# tsl3301cl_cs_mount.net
KiCad netlist of a schematic drawn in EAGLE
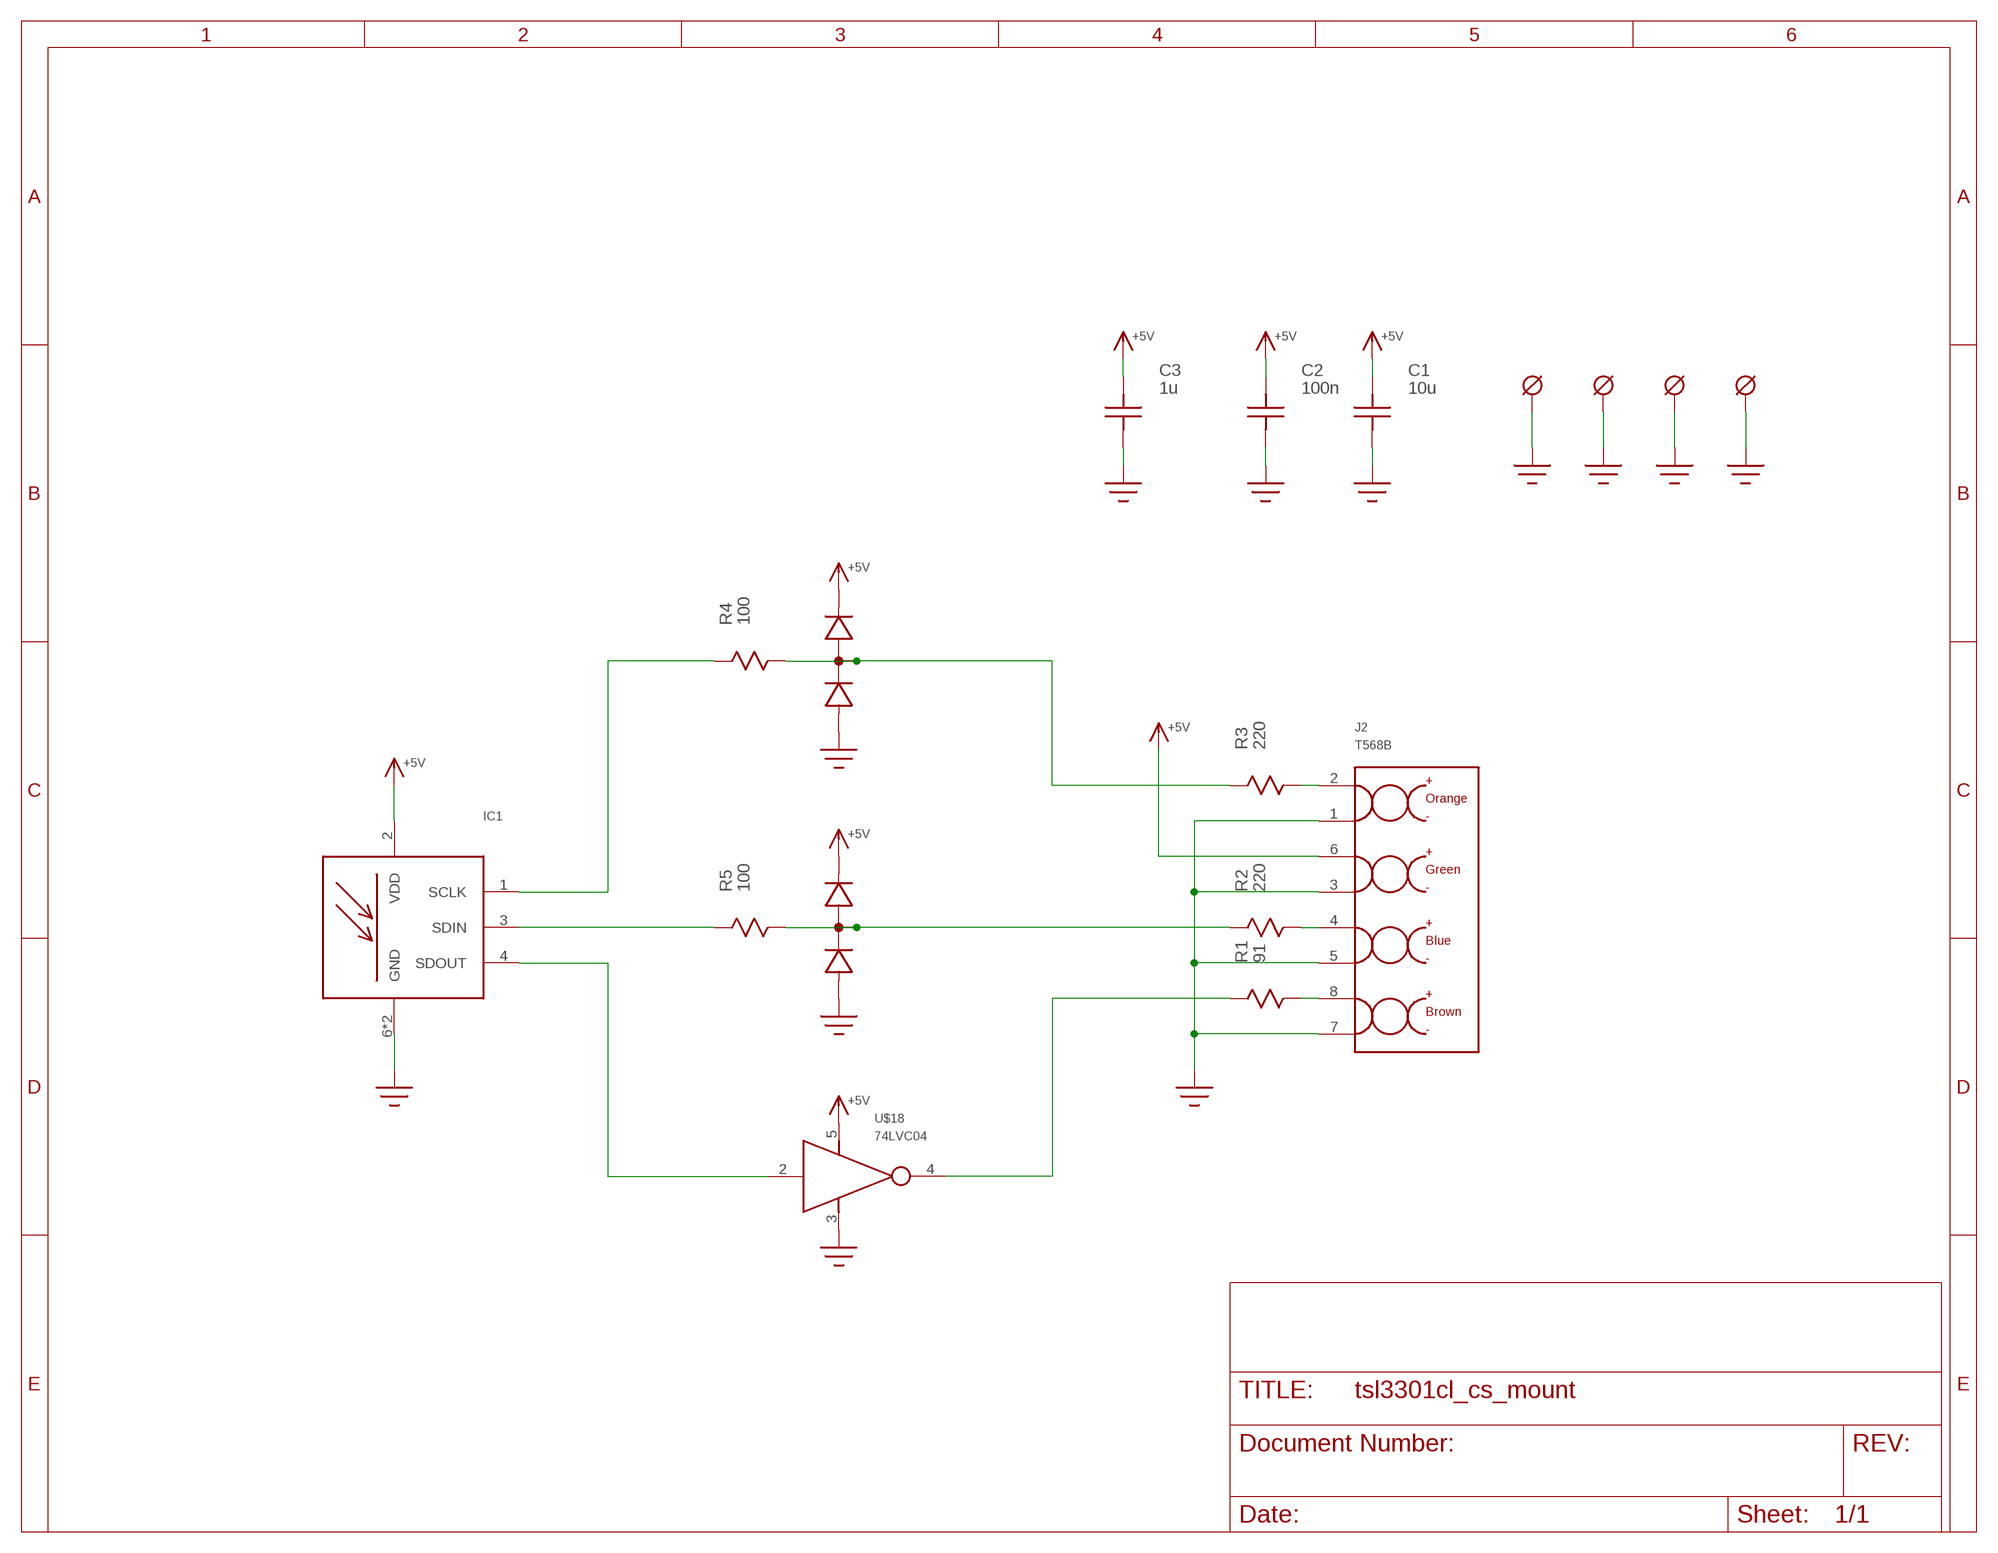
[diagram p0: schematic, sheet 1]

(export (version "E")
  (design (tool "Eeschema 10.0.6"))
  (components
    (comp (ref "C1")
      (value "10u")
      (footprint "eagle-import:1206")
      (libsource (lib "eagle-import") (part "C1206"))
    )
    (comp (ref "C2")
      (value "100n")
      (footprint "eagle-import:C0603")
      (libsource (lib "eagle-import") (part "C0603"))
    )
    (comp (ref "C3")
      (value "1u")
      (footprint "eagle-import:0805")
      (libsource (lib "eagle-import") (part "C0805"))
    )
    (comp (ref "IC1")
      (value "TSL3301CL")
      (footprint "eagle-import:TSL3301")
      (libsource (lib "eagle-import") (part "TSL3301CL"))
    )
    (comp (ref "J2")
      (value "T568B")
      (footprint "eagle-import:RJ45_KEYSTONE_949")
      (libsource (lib "eagle-import") (part "RJ45"))
    )
    (comp (ref "R1")
      (value "91")
      (footprint "eagle-import:R0805")
      (libsource (lib "eagle-import") (part "R0805"))
    )
    (comp (ref "R2")
      (value "220")
      (footprint "eagle-import:R0805")
      (libsource (lib "eagle-import") (part "R0805"))
    )
    (comp (ref "R3")
      (value "220")
      (footprint "eagle-import:R0805")
      (libsource (lib "eagle-import") (part "R0805"))
    )
    (comp (ref "R4")
      (value "100")
      (footprint "eagle-import:R0603")
      (libsource (lib "eagle-import") (part "R0603"))
    )
    (comp (ref "R5")
      (value "100")
      (footprint "eagle-import:R0603")
      (libsource (lib "eagle-import") (part "R0603"))
    )
    (comp (ref "U$2")
      (value "MOUNTING_HOLE")
      (footprint "eagle-import:MOUNTING_HOLE_#4")
      (libsource (lib "eagle-import") (part "MOUNTING_HOLE"))
    )
    (comp (ref "U$3")
      (value "MOUNTING_HOLE")
      (footprint "eagle-import:MOUNTING_HOLE_#4")
      (libsource (lib "eagle-import") (part "MOUNTING_HOLE"))
    )
    (comp (ref "U$4")
      (value "MOUNTING_HOLE")
      (footprint "eagle-import:MOUNTING_HOLE_#4")
      (libsource (lib "eagle-import") (part "MOUNTING_HOLE"))
    )
    (comp (ref "U$5")
      (value "MOUNTING_HOLE")
      (footprint "eagle-import:MOUNTING_HOLE_#4")
      (libsource (lib "eagle-import") (part "MOUNTING_HOLE"))
    )
    (comp (ref "U$18")
      (value "74LVC04")
      (footprint "eagle-import:SOT23-5")
      (libsource (lib "eagle-import") (part "74LVC04"))
    )
    (comp (ref "U$21")
      (value "MMBD7000L")
      (footprint "eagle-import:SOT-23")
      (libsource (lib "eagle-import") (part "MMBD7000L"))
    )
    (comp (ref "U$22")
      (value "MMBD7000L")
      (footprint "eagle-import:SOT-23")
      (libsource (lib "eagle-import") (part "MMBD7000L"))
    )
  )
  (nets
    (net (code "1") (name "+5V") (class "Default")
      (node (ref "C1") (pin "P$2") (pinfunction "P$2_P$2") (pintype "bidirectional"))
      (node (ref "C2") (pin "P$2") (pinfunction "P$2_P$2") (pintype "bidirectional"))
      (node (ref "C3") (pin "P$2") (pinfunction "P$2_P$2") (pintype "bidirectional"))
      (node (ref "IC1") (pin "2") (pinfunction "VDD_2") (pintype "bidirectional"))
      (node (ref "J2") (pin "6") (pinfunction "6_6") (pintype "bidirectional"))
      (node (ref "U$18") (pin "5") (pinfunction "VCC_5") (pintype "bidirectional"))
      (node (ref "U$21") (pin "2") (pinfunction "CATHODE_2") (pintype "bidirectional"))
      (node (ref "U$22") (pin "2") (pinfunction "CATHODE_2") (pintype "bidirectional"))
    )
    (net (code "2") (name "GND") (class "Default")
      (node (ref "C1") (pin "P$1") (pinfunction "P$1_P$1") (pintype "bidirectional"))
      (node (ref "C2") (pin "P$1") (pinfunction "P$1_P$1") (pintype "bidirectional"))
      (node (ref "C3") (pin "P$1") (pinfunction "P$1_P$1") (pintype "bidirectional"))
      (node (ref "IC1") (pin "6") (pinfunction "GND_6") (pintype "bidirectional"))
      (node (ref "IC1") (pin "7") (pinfunction "GND_7") (pintype "bidirectional"))
      (node (ref "J2") (pin "1") (pinfunction "1_1") (pintype "bidirectional"))
      (node (ref "J2") (pin "3") (pinfunction "3_3") (pintype "bidirectional"))
      (node (ref "J2") (pin "5") (pinfunction "5_5") (pintype "bidirectional"))
      (node (ref "J2") (pin "7") (pinfunction "7_7") (pintype "bidirectional"))
      (node (ref "U$18") (pin "3") (pinfunction "GND_3") (pintype "bidirectional"))
      (node (ref "U$2") (pin "P$1") (pinfunction "P$1_P$1") (pintype "bidirectional"))
      (node (ref "U$2") (pin "P$2") (pinfunction "P$1_P$2") (pintype "bidirectional"))
      (node (ref "U$2") (pin "P$3") (pinfunction "P$1_P$3") (pintype "bidirectional"))
      (node (ref "U$2") (pin "P$4") (pinfunction "P$1_P$4") (pintype "bidirectional"))
      (node (ref "U$2") (pin "P$5") (pinfunction "P$1_P$5") (pintype "bidirectional"))
      (node (ref "U$2") (pin "P$6") (pinfunction "P$1_P$6") (pintype "bidirectional"))
      (node (ref "U$2") (pin "P$7") (pinfunction "P$1_P$7") (pintype "bidirectional"))
      (node (ref "U$2") (pin "P$8") (pinfunction "P$1_P$8") (pintype "bidirectional"))
      (node (ref "U$2") (pin "P$9") (pinfunction "P$1_P$9") (pintype "bidirectional"))
      (node (ref "U$21") (pin "1") (pinfunction "ANODE_1") (pintype "bidirectional"))
      (node (ref "U$22") (pin "1") (pinfunction "ANODE_1") (pintype "bidirectional"))
      (node (ref "U$3") (pin "P$1") (pinfunction "P$1_P$1") (pintype "bidirectional"))
      (node (ref "U$3") (pin "P$2") (pinfunction "P$1_P$2") (pintype "bidirectional"))
      (node (ref "U$3") (pin "P$3") (pinfunction "P$1_P$3") (pintype "bidirectional"))
      (node (ref "U$3") (pin "P$4") (pinfunction "P$1_P$4") (pintype "bidirectional"))
      (node (ref "U$3") (pin "P$5") (pinfunction "P$1_P$5") (pintype "bidirectional"))
      (node (ref "U$3") (pin "P$6") (pinfunction "P$1_P$6") (pintype "bidirectional"))
      (node (ref "U$3") (pin "P$7") (pinfunction "P$1_P$7") (pintype "bidirectional"))
      (node (ref "U$3") (pin "P$8") (pinfunction "P$1_P$8") (pintype "bidirectional"))
      (node (ref "U$3") (pin "P$9") (pinfunction "P$1_P$9") (pintype "bidirectional"))
      (node (ref "U$4") (pin "P$1") (pinfunction "P$1_P$1") (pintype "bidirectional"))
      (node (ref "U$4") (pin "P$2") (pinfunction "P$1_P$2") (pintype "bidirectional"))
      (node (ref "U$4") (pin "P$3") (pinfunction "P$1_P$3") (pintype "bidirectional"))
      (node (ref "U$4") (pin "P$4") (pinfunction "P$1_P$4") (pintype "bidirectional"))
      (node (ref "U$4") (pin "P$5") (pinfunction "P$1_P$5") (pintype "bidirectional"))
      (node (ref "U$4") (pin "P$6") (pinfunction "P$1_P$6") (pintype "bidirectional"))
      (node (ref "U$4") (pin "P$7") (pinfunction "P$1_P$7") (pintype "bidirectional"))
      (node (ref "U$4") (pin "P$8") (pinfunction "P$1_P$8") (pintype "bidirectional"))
      (node (ref "U$4") (pin "P$9") (pinfunction "P$1_P$9") (pintype "bidirectional"))
      (node (ref "U$5") (pin "P$1") (pinfunction "P$1_P$1") (pintype "bidirectional"))
      (node (ref "U$5") (pin "P$2") (pinfunction "P$1_P$2") (pintype "bidirectional"))
      (node (ref "U$5") (pin "P$3") (pinfunction "P$1_P$3") (pintype "bidirectional"))
      (node (ref "U$5") (pin "P$4") (pinfunction "P$1_P$4") (pintype "bidirectional"))
      (node (ref "U$5") (pin "P$5") (pinfunction "P$1_P$5") (pintype "bidirectional"))
      (node (ref "U$5") (pin "P$6") (pinfunction "P$1_P$6") (pintype "bidirectional"))
      (node (ref "U$5") (pin "P$7") (pinfunction "P$1_P$7") (pintype "bidirectional"))
      (node (ref "U$5") (pin "P$8") (pinfunction "P$1_P$8") (pintype "bidirectional"))
      (node (ref "U$5") (pin "P$9") (pinfunction "P$1_P$9") (pintype "bidirectional"))
    )
    (net (code "3") (name "Net-(IC1-SCLK)") (class "Default")
      (node (ref "IC1") (pin "1") (pinfunction "SCLK_1") (pintype "bidirectional"))
      (node (ref "R4") (pin "P$1") (pinfunction "P$3_P$1") (pintype "bidirectional"))
    )
    (net (code "4") (name "Net-(IC1-SDIN)") (class "Default")
      (node (ref "IC1") (pin "3") (pinfunction "SDIN_3") (pintype "bidirectional"))
      (node (ref "R5") (pin "P$1") (pinfunction "P$3_P$1") (pintype "bidirectional"))
    )
    (net (code "5") (name "Net-(IC1-SDOUT)") (class "Default")
      (node (ref "IC1") (pin "4") (pinfunction "SDOUT_4") (pintype "bidirectional"))
      (node (ref "U$18") (pin "2") (pinfunction "IN_2") (pintype "bidirectional"))
    )
    (net (code "6") (name "Net-(R1-P$3)") (class "Default")
      (node (ref "R1") (pin "P$1") (pinfunction "P$3_P$1") (pintype "bidirectional"))
      (node (ref "U$18") (pin "4") (pinfunction "OUT_4") (pintype "bidirectional"))
    )
    (net (code "7") (name "Net-(R1-P$4)") (class "Default")
      (node (ref "J2") (pin "8") (pinfunction "8_8") (pintype "bidirectional"))
      (node (ref "R1") (pin "P$2") (pinfunction "P$4_P$2") (pintype "bidirectional"))
    )
    (net (code "8") (name "Net-(R2-P$3)") (class "Default")
      (node (ref "R2") (pin "P$1") (pinfunction "P$3_P$1") (pintype "bidirectional"))
      (node (ref "R5") (pin "P$2") (pinfunction "P$4_P$2") (pintype "bidirectional"))
      (node (ref "U$21") (pin "3") (pinfunction "COMMON_3") (pintype "bidirectional"))
    )
    (net (code "9") (name "Net-(R2-P$4)") (class "Default")
      (node (ref "J2") (pin "4") (pinfunction "4_4") (pintype "bidirectional"))
      (node (ref "R2") (pin "P$2") (pinfunction "P$4_P$2") (pintype "bidirectional"))
    )
    (net (code "10") (name "Net-(R3-P$3)") (class "Default")
      (node (ref "R3") (pin "P$1") (pinfunction "P$3_P$1") (pintype "bidirectional"))
      (node (ref "R4") (pin "P$2") (pinfunction "P$4_P$2") (pintype "bidirectional"))
      (node (ref "U$22") (pin "3") (pinfunction "COMMON_3") (pintype "bidirectional"))
    )
    (net (code "11") (name "Net-(R3-P$4)") (class "Default")
      (node (ref "J2") (pin "2") (pinfunction "2_2") (pintype "bidirectional"))
      (node (ref "R3") (pin "P$2") (pinfunction "P$4_P$2") (pintype "bidirectional"))
    )
  )
)
